# Load_Cell_Board.net
KiCad netlist of a schematic drawn in Altium Designer
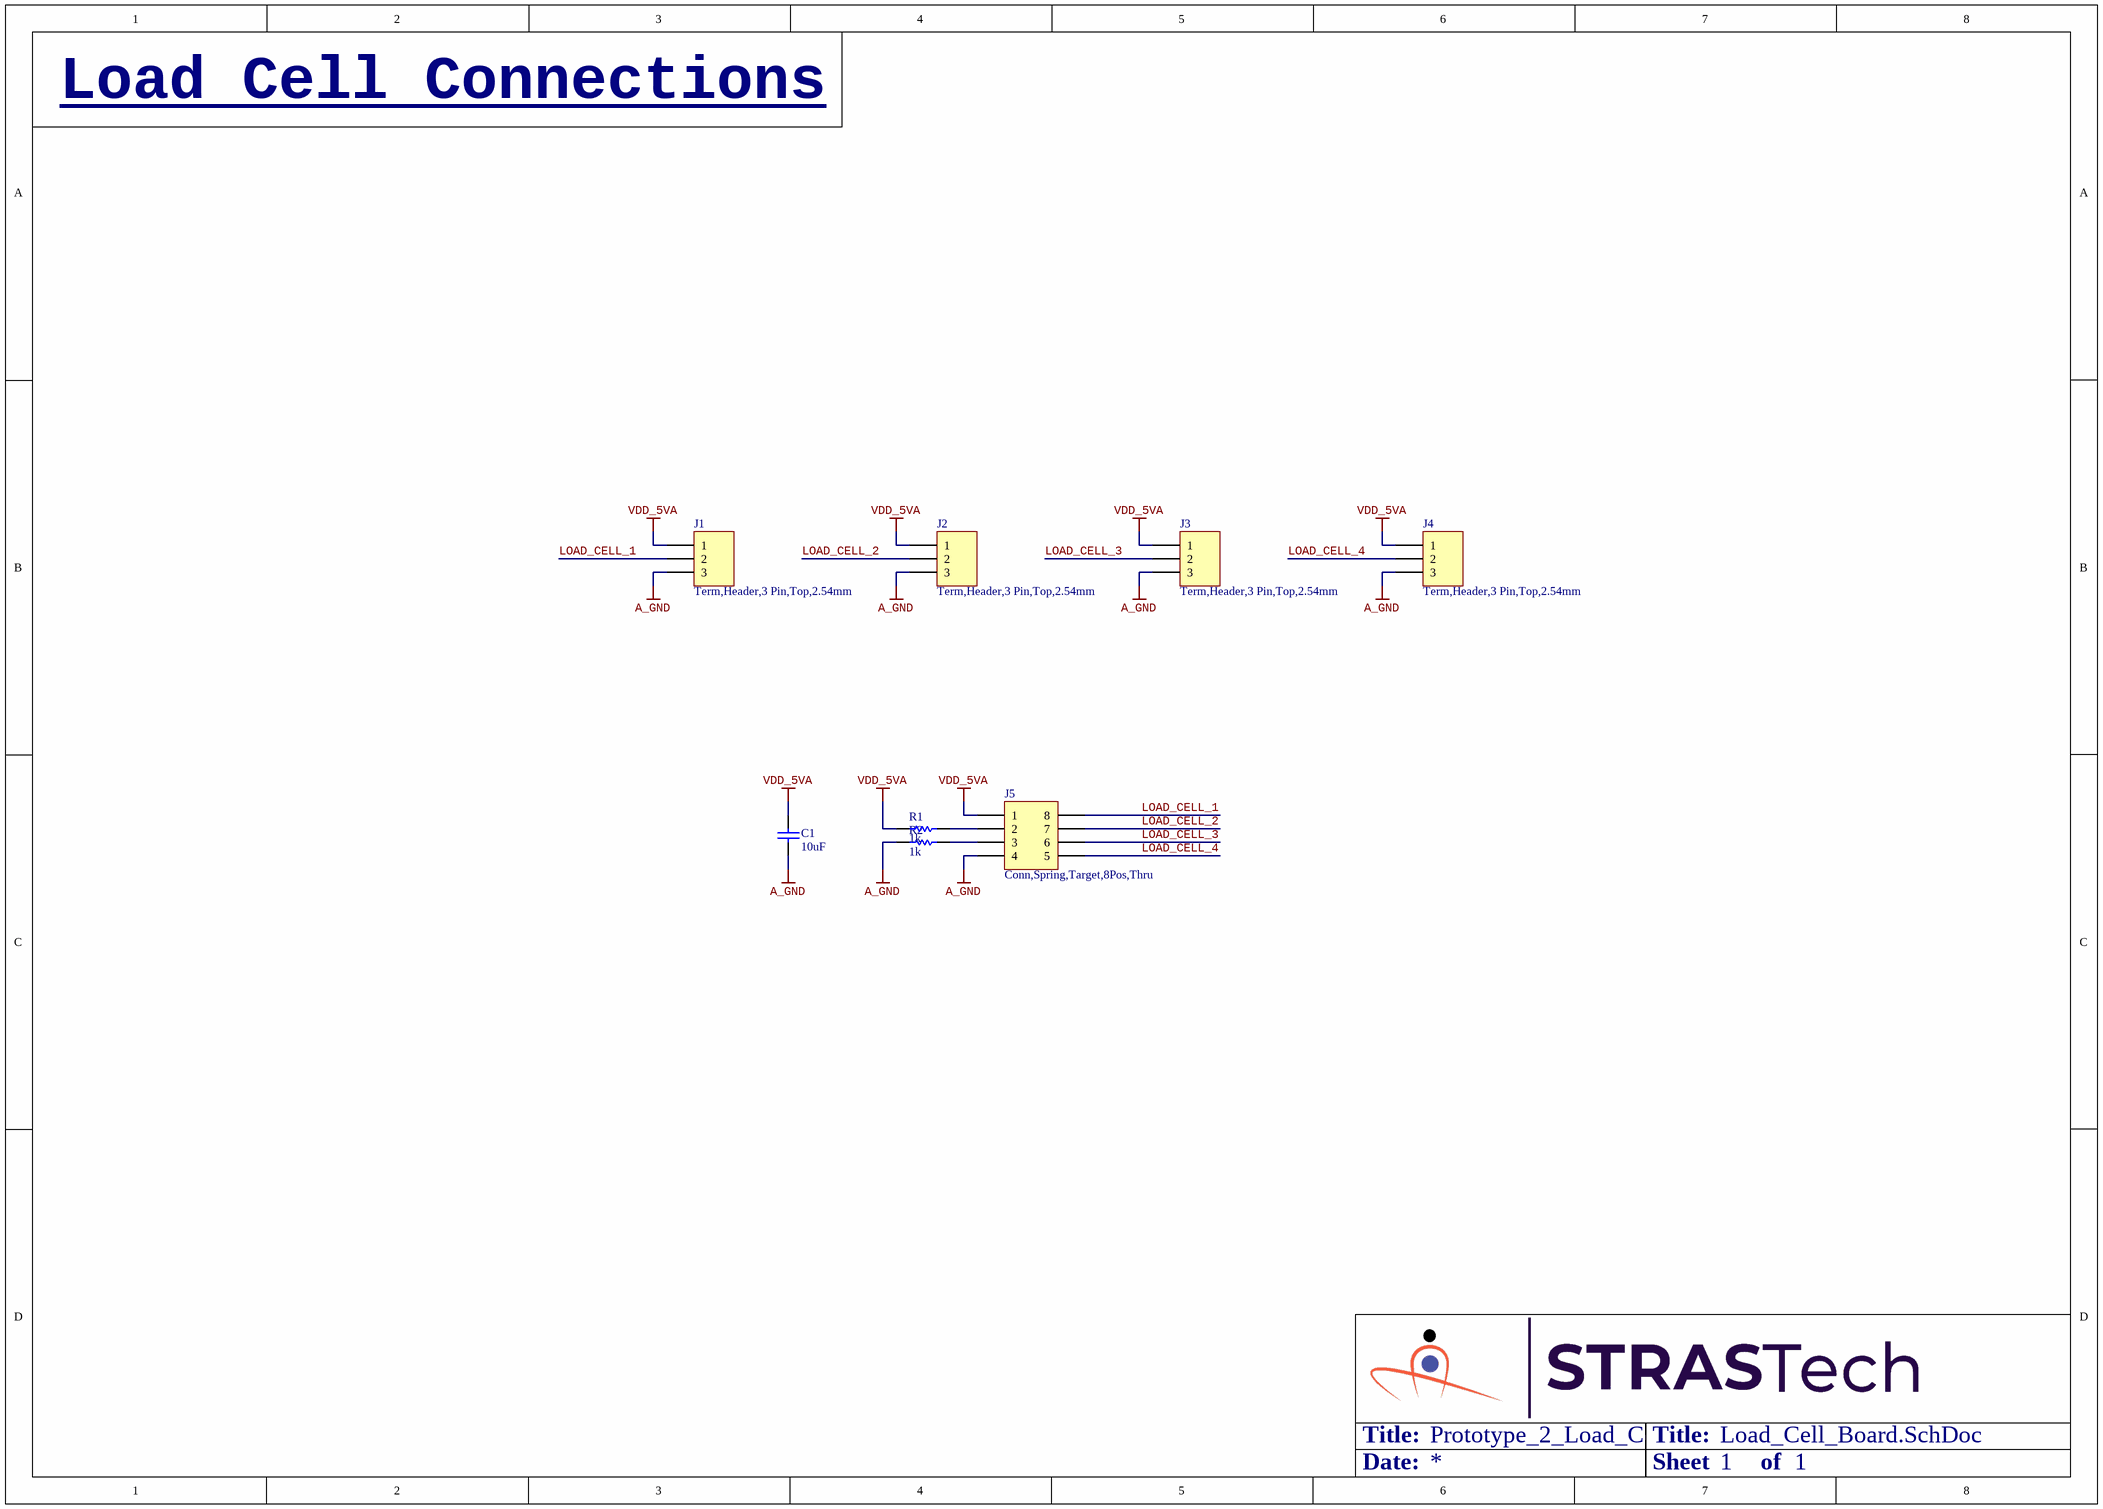
[diagram p0: Load_Cell_Board.SchDoc]

(export (version "E")
  (design (tool "Eeschema 10.0.6"))
  (components
    (comp (ref "C1")
      (value "10uF")
      (footprint "Cap,SMD,0402")
      (description "10 µF ±20% 10V Ceramic Capacitor X5R 0402 (1005 Metric)")
      (fields
        (field (name "VENDOR PART NUMBER") "1276-1450-1-ND")
        (field (name "MANUFACTURER") "Samsung Electro-Mechanics")
        (field (name "CREATEDBY") "Judd Foster")
      )
      (libsource (lib "symbols") (part "CAP,Cer,10uF,10VDC,X5R,0402"))
    )
    (comp (ref "J1")
      (value "Term,Header,3 Pin,Top,2.54mm")
      (footprint "Term,Header,3Pin,2.54mm")
      (description "CONN HEADER VERT 3POS 2.54MM")
      (fields
        (field (name "VENDOR PART NUMBER") "732-5316-ND")
        (field (name "MANUFACTURER") "Würth Elektronik")
        (field (name "CREATED BY") "Judd Foster")
      )
      (libsource (lib "symbols") (part "Term,Header,3 Pin,Top,2.54mm"))
    )
    (comp (ref "J2")
      (value "Term,Header,3 Pin,Top,2.54mm")
      (footprint "Term,Header,3Pin,2.54mm")
      (description "CONN HEADER VERT 3POS 2.54MM")
      (fields
        (field (name "VENDOR PART NUMBER") "732-5316-ND")
        (field (name "MANUFACTURER") "Würth Elektronik")
        (field (name "CREATED BY") "Judd Foster")
      )
      (libsource (lib "symbols") (part "Term,Header,3 Pin,Top,2.54mm"))
    )
    (comp (ref "J3")
      (value "Term,Header,3 Pin,Top,2.54mm")
      (footprint "Term,Header,3Pin,2.54mm")
      (description "CONN HEADER VERT 3POS 2.54MM")
      (fields
        (field (name "VENDOR PART NUMBER") "732-5316-ND")
        (field (name "MANUFACTURER") "Würth Elektronik")
        (field (name "CREATED BY") "Judd Foster")
      )
      (libsource (lib "symbols") (part "Term,Header,3 Pin,Top,2.54mm"))
    )
    (comp (ref "J4")
      (value "Term,Header,3 Pin,Top,2.54mm")
      (footprint "Term,Header,3Pin,2.54mm")
      (description "CONN HEADER VERT 3POS 2.54MM")
      (fields
        (field (name "VENDOR PART NUMBER") "732-5316-ND")
        (field (name "MANUFACTURER") "Würth Elektronik")
        (field (name "CREATED BY") "Judd Foster")
      )
      (libsource (lib "symbols") (part "Term,Header,3 Pin,Top,2.54mm"))
    )
    (comp (ref "J5")
      (value "Conn,Spring,Target,8Pos,Thru")
      (footprint "Conn,Spring,Target,8Pos,Thru")
      (description "8 Position Spring Mating Target Connector Through Hole")
      (fields
        (field (name "MANUFACTURER") "Mill-Max Manufacturing Corp.")
        (field (name "MANUFACTURER PART NUMBER") "419-10-208-00-006000")
        (field (name "CREATEDBY") "Judd Foster")
      )
      (libsource (lib "symbols") (part "Conn,Spring,Target,8Pos,Thru"))
    )
    (comp (ref "R1")
      (value "1k")
      (footprint "RES,0402")
      (description "1 kOhms ±5% 0.063W, 1/16W Chip Resistor 0402 (1005 Metric) Automotive AEC-Q200 Thick Film")
      (fields
        (field (name "VENDOR PART NUMBER") "RMCF0402JT1K00CT-ND")
        (field (name "MANUFACTURER") "Stackpole Electronics Inc")
        (field (name "CREATEDBY") "Judd Foster")
      )
      (libsource (lib "symbols") (part "RES,1k,5%,0.063W,0402"))
    )
    (comp (ref "R2")
      (value "1k")
      (footprint "RES,0402")
      (description "1 kOhms ±5% 0.063W, 1/16W Chip Resistor 0402 (1005 Metric) Automotive AEC-Q200 Thick Film")
      (fields
        (field (name "VENDOR PART NUMBER") "RMCF0402JT1K00CT-ND")
        (field (name "MANUFACTURER") "Stackpole Electronics Inc")
        (field (name "CREATEDBY") "Judd Foster")
      )
      (libsource (lib "symbols") (part "RES,1k,5%,0.063W,0402"))
    )
  )
  (nets
    (net (code "1") (name "/LOAD_CELL_1") (class "Default")
      (node (ref "J1") (pin "2") (pinfunction "2_2") (pintype "passive"))
      (node (ref "J5") (pin "8") (pinfunction "8_8") (pintype "passive"))
    )
    (net (code "2") (name "/LOAD_CELL_2") (class "Default")
      (node (ref "J2") (pin "2") (pinfunction "2_2") (pintype "passive"))
      (node (ref "J5") (pin "7") (pinfunction "7_7") (pintype "passive"))
    )
    (net (code "3") (name "/LOAD_CELL_3") (class "Default")
      (node (ref "J3") (pin "2") (pinfunction "2_2") (pintype "passive"))
      (node (ref "J5") (pin "6") (pinfunction "6_6") (pintype "passive"))
    )
    (net (code "4") (name "/LOAD_CELL_4") (class "Default")
      (node (ref "J4") (pin "2") (pinfunction "2_2") (pintype "passive"))
      (node (ref "J5") (pin "5") (pinfunction "5_5") (pintype "passive"))
    )
    (net (code "5") (name "A_GND") (class "Default")
      (node (ref "C1") (pin "1") (pinfunction "1_1") (pintype "passive"))
      (node (ref "J1") (pin "3") (pinfunction "3_3") (pintype "passive"))
      (node (ref "J2") (pin "3") (pinfunction "3_3") (pintype "passive"))
      (node (ref "J3") (pin "3") (pinfunction "3_3") (pintype "passive"))
      (node (ref "J4") (pin "3") (pinfunction "3_3") (pintype "passive"))
      (node (ref "J5") (pin "4") (pinfunction "4_4") (pintype "passive"))
      (node (ref "R2") (pin "1") (pinfunction "1_1") (pintype "passive"))
    )
    (net (code "6") (name "Net-(J5-Pad2)") (class "Default")
      (node (ref "J5") (pin "2") (pinfunction "2_2") (pintype "passive"))
      (node (ref "R1") (pin "2") (pinfunction "2_2") (pintype "passive"))
    )
    (net (code "7") (name "Net-(J5-Pad3)") (class "Default")
      (node (ref "J5") (pin "3") (pinfunction "3_3") (pintype "passive"))
      (node (ref "R2") (pin "2") (pinfunction "2_2") (pintype "passive"))
    )
    (net (code "8") (name "VDD_5VA") (class "Default")
      (node (ref "C1") (pin "2") (pinfunction "2_2") (pintype "passive"))
      (node (ref "J1") (pin "1") (pinfunction "1_1") (pintype "passive"))
      (node (ref "J2") (pin "1") (pinfunction "1_1") (pintype "passive"))
      (node (ref "J3") (pin "1") (pinfunction "1_1") (pintype "passive"))
      (node (ref "J4") (pin "1") (pinfunction "1_1") (pintype "passive"))
      (node (ref "J5") (pin "1") (pinfunction "1_1") (pintype "passive"))
      (node (ref "R1") (pin "1") (pinfunction "1_1") (pintype "passive"))
    )
  )
)
